# sensor_luz.net
KiCad netlist of a schematic drawn in EAGLE
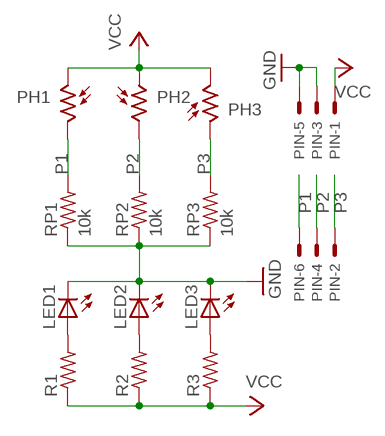
[diagram p0: schematic, sheet 1]

(export (version "E")
  (design (tool "Eeschema 10.0.6"))
  (components
    (comp (ref "LED1")
      (value "LED3MM")
      (footprint "eagle-import:LED3MM")
      (libsource (lib "eagle-import") (part "LED3MM"))
    )
    (comp (ref "LED2")
      (value "LED3MM")
      (footprint "eagle-import:LED3MM")
      (libsource (lib "eagle-import") (part "LED3MM"))
    )
    (comp (ref "LED3")
      (value "LED3MM")
      (footprint "eagle-import:LED3MM")
      (libsource (lib "eagle-import") (part "LED3MM"))
    )
    (comp (ref "PH1")
      (value "VT20N4")
      (footprint "eagle-import:TO46-VT200")
      (libsource (lib "eagle-import") (part "VT20N4"))
    )
    (comp (ref "PH2")
      (value "VT20N4")
      (footprint "eagle-import:TO46-VT200")
      (libsource (lib "eagle-import") (part "VT20N4"))
    )
    (comp (ref "PH3")
      (value "VT20N4")
      (footprint "eagle-import:TO46-VT200")
      (libsource (lib "eagle-import") (part "VT20N4"))
    )
    (comp (ref "PIN")
      (value "332-06")
      (footprint "eagle-import:332-06")
      (libsource (lib "eagle-import") (part "332-06"))
    )
    (comp (ref "R1")
      (value "R-US_0207/7")
      (footprint "eagle-import:0207_7")
      (libsource (lib "eagle-import") (part "R-US_0207/7"))
    )
    (comp (ref "R2")
      (value "R-US_0207/7")
      (footprint "eagle-import:0207_7")
      (libsource (lib "eagle-import") (part "R-US_0207/7"))
    )
    (comp (ref "R3")
      (value "R-US_0207/7")
      (footprint "eagle-import:0207_7")
      (libsource (lib "eagle-import") (part "R-US_0207/7"))
    )
    (comp (ref "RP1")
      (value "10k")
      (footprint "eagle-import:0207_7")
      (libsource (lib "eagle-import") (part "R-US_0207/7"))
    )
    (comp (ref "RP2")
      (value "10k")
      (footprint "eagle-import:0207_7")
      (libsource (lib "eagle-import") (part "R-US_0207/7"))
    )
    (comp (ref "RP3")
      (value "10k")
      (footprint "eagle-import:0207_7")
      (libsource (lib "eagle-import") (part "R-US_0207/7"))
    )
  )
  (nets
    (net (code "1") (name "/P1") (class "Default")
      (node (ref "PH1") (pin "2") (pinfunction "2_2") (pintype "passive"))
      (node (ref "PIN") (pin "6") (pinfunction "S_6") (pintype "passive"))
      (node (ref "RP1") (pin "2") (pinfunction "2_2") (pintype "passive"))
    )
    (net (code "2") (name "/P2") (class "Default")
      (node (ref "PH2") (pin "2") (pinfunction "2_2") (pintype "passive"))
      (node (ref "PIN") (pin "4") (pinfunction "S_4") (pintype "passive"))
      (node (ref "RP2") (pin "2") (pinfunction "2_2") (pintype "passive"))
    )
    (net (code "3") (name "/P3") (class "Default")
      (node (ref "PH3") (pin "1") (pinfunction "1_1") (pintype "passive"))
      (node (ref "PIN") (pin "2") (pinfunction "S_2") (pintype "passive"))
      (node (ref "RP3") (pin "2") (pinfunction "2_2") (pintype "passive"))
    )
    (net (code "4") (name "GND") (class "Default")
      (node (ref "LED1") (pin "K") (pinfunction "C_K") (pintype "passive"))
      (node (ref "LED2") (pin "K") (pinfunction "C_K") (pintype "passive"))
      (node (ref "LED3") (pin "K") (pinfunction "C_K") (pintype "passive"))
      (node (ref "PIN") (pin "3") (pinfunction "S_3") (pintype "passive"))
      (node (ref "PIN") (pin "5") (pinfunction "S_5") (pintype "passive"))
      (node (ref "RP1") (pin "1") (pinfunction "1_1") (pintype "passive"))
      (node (ref "RP2") (pin "1") (pinfunction "1_1") (pintype "passive"))
      (node (ref "RP3") (pin "1") (pinfunction "1_1") (pintype "passive"))
    )
    (net (code "5") (name "Net-(LED1-PadA)") (class "Default")
      (node (ref "LED1") (pin "A") (pinfunction "A_A") (pintype "passive"))
      (node (ref "R1") (pin "2") (pinfunction "2_2") (pintype "passive"))
    )
    (net (code "6") (name "Net-(LED2-PadA)") (class "Default")
      (node (ref "LED2") (pin "A") (pinfunction "A_A") (pintype "passive"))
      (node (ref "R2") (pin "2") (pinfunction "2_2") (pintype "passive"))
    )
    (net (code "7") (name "Net-(LED3-PadA)") (class "Default")
      (node (ref "LED3") (pin "A") (pinfunction "A_A") (pintype "passive"))
      (node (ref "R3") (pin "2") (pinfunction "2_2") (pintype "passive"))
    )
    (net (code "8") (name "VCC") (class "Default")
      (node (ref "PH1") (pin "1") (pinfunction "1_1") (pintype "passive"))
      (node (ref "PH2") (pin "1") (pinfunction "1_1") (pintype "passive"))
      (node (ref "PH3") (pin "2") (pinfunction "2_2") (pintype "passive"))
      (node (ref "PIN") (pin "1") (pinfunction "S_1") (pintype "passive"))
      (node (ref "R1") (pin "1") (pinfunction "1_1") (pintype "passive"))
      (node (ref "R2") (pin "1") (pinfunction "1_1") (pintype "passive"))
      (node (ref "R3") (pin "1") (pinfunction "1_1") (pintype "passive"))
    )
  )
)
